# cf2loco.net
KiCad netlist of a schematic drawn in Altium Designer
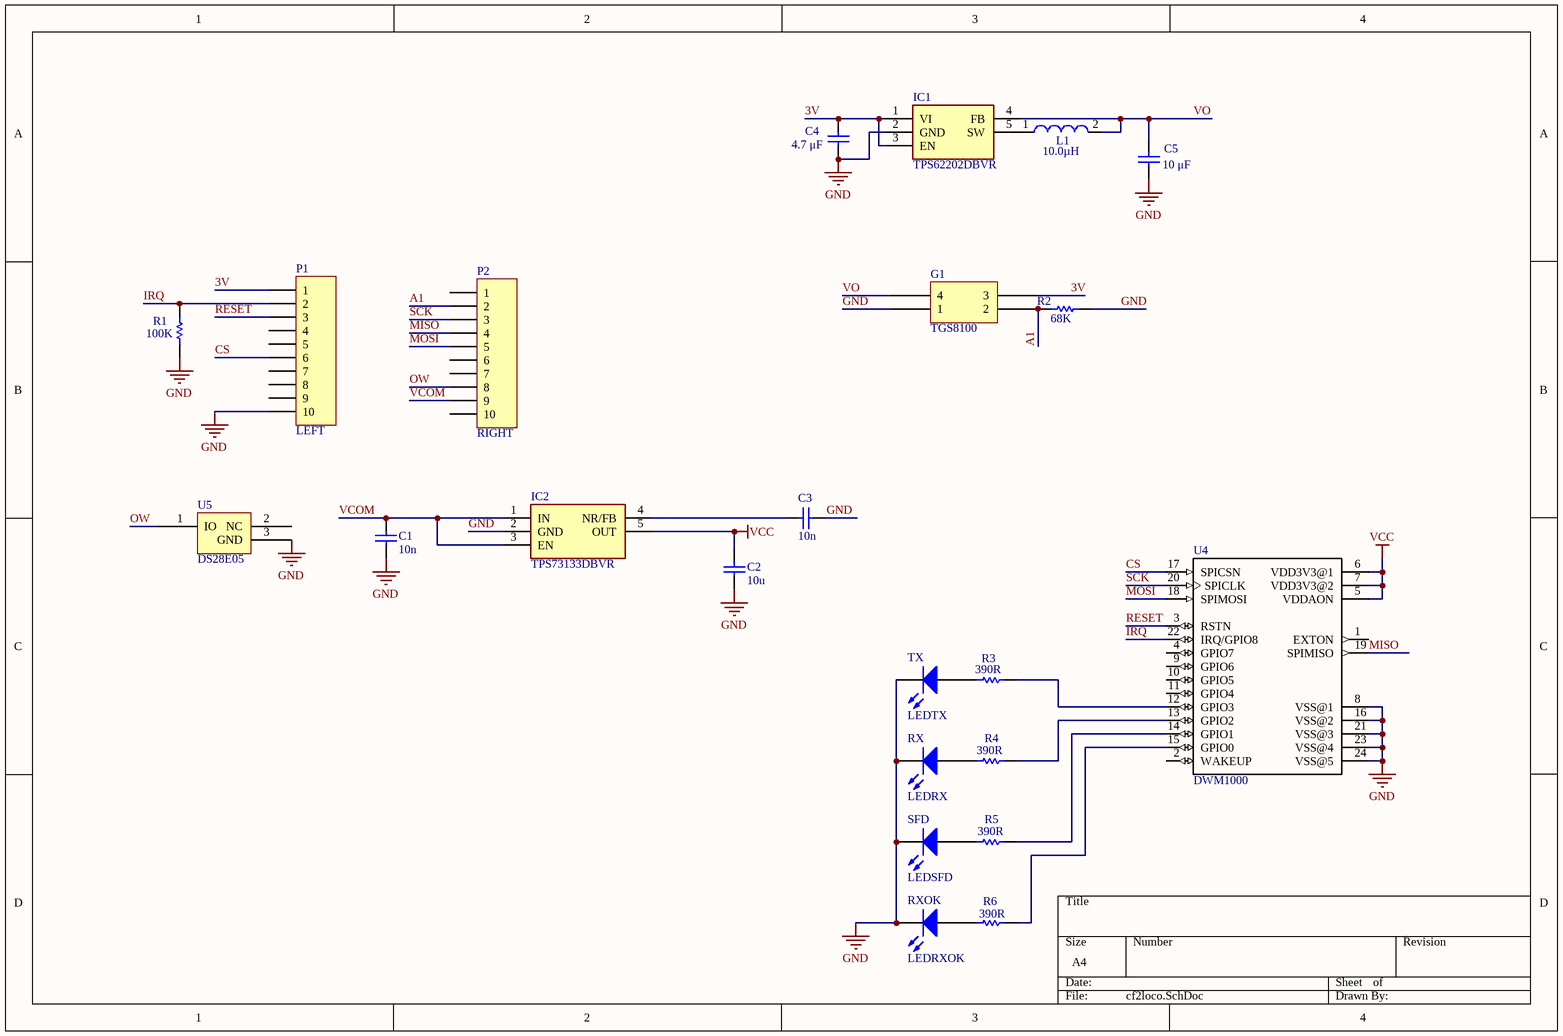
[diagram p0: cf2loco.SchDoc]

(export (version "E")
  (design (tool "Eeschema 10.0.6"))
  (components
    (comp (ref "C1")
      (value "10n")
      (footprint "0402-A")
      (description "Capacitor")
      (fields (field (name "Comment") "Cap") (field (name "PUBLISHER") "Altium Limited"))
      (libsource (lib "Miscellaneous Devices") (part "Cap"))
    )
    (comp (ref "C2")
      (value "10u")
      (footprint "0603")
      (description "Capacitor")
      (fields (field (name "Comment") "Cap") (field (name "PUBLISHER") "Altium Limited"))
      (libsource (lib "Miscellaneous Devices") (part "Cap"))
    )
    (comp (ref "C3")
      (value "10n")
      (footprint "0402-A")
      (description "Capacitor")
      (fields (field (name "Comment") "Cap") (field (name "PUBLISHER") "Altium Limited"))
      (libsource (lib "Miscellaneous Devices") (part "Cap"))
    )
    (comp (ref "C4")
      (value "06036D475KAT2A")
      (footprint "CAPC1608X90X35LL15T15")
      (fields (field (name "MANUFACTURER") "AVX Interconnect / Elco") (field (name "PARAMETER 1") "4.7 μF"))
      (libsource (lib "Altium Content Vault") (part "CAP"))
    )
    (comp (ref "C5")
      (value "06036D106MAT2A")
      (footprint "CAPC1608X90X35ML15T15")
      (fields (field (name "MANUFACTURER") "AVX Interconnect / Elco") (field (name "PARAMETER 1") "10 μF"))
      (libsource (lib "Altium Content Vault") (part "CAP"))
    )
    (comp (ref "G1") (value "TGS8100") (footprint "TGS8100") (libsource (lib "cf2loco") (part "TGS8100")))
    (comp (ref "IC1")
      (value "TPS62202DBVR")
      (footprint "SamacSys:SOT95P280X145-5N")
      (description "Integrated Circuit")
      (libsource (lib "*") (part "TPS62202DBVR"))
    )
    (comp (ref "IC2")
      (value "TPS73133DBVR")
      (footprint "SamacSys:SOT95P280X145-5N")
      (description "Integrated Circuit")
      (fields (field (name "MOUSER2 PART NUMBER") "595-TPS73133DBVR"))
      (libsource (lib "*") (part "TPS73133DBVR"))
    )
    (comp (ref "L1")
      (value "744031100")
      (footprint "WE-TPC-3816-S")
      (description "SMD Shielded Tiny Power Inductor WE-TPC, L = 10.0 µH")
      (fields (field (name "INDUCTANCE") "10.0µH"))
      (libsource (lib "Altium Content Vault") (part "PAS-IND-INDUCTOR-2"))
    )
    (comp (ref "P1")
      (value "LEFT")
      (footprint "CFHEADER")
      (description "Header, 10-Pin")
      (fields (field (name "PUBLISHER") "Altium Limited"))
      (libsource (lib "Miscellaneous Connectors") (part "Header 10"))
    )
    (comp (ref "P2")
      (value "RIGHT")
      (footprint "CFHEADER")
      (description "Header, 10-Pin")
      (fields (field (name "PUBLISHER") "Altium Limited"))
      (libsource (lib "Miscellaneous Connectors") (part "Header 10"))
    )
    (comp (ref "R1")
      (value "CRCW0805100KFKEA")
      (footprint "RESC2013X50X30NL20T20")
      (fields (field (name "MANUFACTURER") "Vishay Dale") (field (name "PARAMETER 1") "100K"))
      (libsource (lib "Altium Content Vault") (part "RES"))
    )
    (comp (ref "R2")
      (value "68K")
      (footprint "RESC0603(1608)_M")
      (description "68K 0.1W 1% 0603 (1608 Metric)  SMD")
      (fields (field (name "POWER") "0.1 W") (field (name "TOLERANCE") "1 %"))
      (libsource (lib "Altium Content Vault") (part "RES"))
    )
    (comp (ref "R3")
      (value "CRCW0805390RFKEA")
      (footprint "RESC2013X50X30NL20T20")
      (fields (field (name "MANUFACTURER") "Vishay Dale") (field (name "PARAMETER 1") "390R"))
      (libsource (lib "Altium Content Vault") (part "RES"))
    )
    (comp (ref "R4")
      (value "CRCW0805390RFKEA")
      (footprint "RESC2013X50X30NL20T20")
      (fields (field (name "MANUFACTURER") "Vishay Dale") (field (name "PARAMETER 1") "390R"))
      (libsource (lib "Altium Content Vault") (part "RES"))
    )
    (comp (ref "R5")
      (value "CRCW0805390RFKEA")
      (footprint "RESC2013X50X30NL20T20")
      (fields (field (name "MANUFACTURER") "Vishay Dale") (field (name "PARAMETER 1") "390R"))
      (libsource (lib "Altium Content Vault") (part "RES"))
    )
    (comp (ref "R6")
      (value "CRCW0805390RFKEA")
      (footprint "RESC2013X50X30NL20T20")
      (fields (field (name "MANUFACTURER") "Vishay Dale") (field (name "PARAMETER 1") "390R"))
      (libsource (lib "Altium Content Vault") (part "RES"))
    )
    (comp (ref "RX")
      (value "LEDRX")
      (footprint "0402-A")
      (description "Typical RED, GREEN, YELLOW, AMBER GaAs LED")
      (fields (field (name "PUBLISHER") "Altium Limited"))
      (libsource (lib "Miscellaneous Devices") (part "LED2"))
    )
    (comp (ref "RXOK")
      (value "LEDRXOK")
      (footprint "0402-A")
      (description "Typical RED, GREEN, YELLOW, AMBER GaAs LED")
      (fields (field (name "PUBLISHER") "Altium Limited"))
      (libsource (lib "Miscellaneous Devices") (part "LED2"))
    )
    (comp (ref "SFD")
      (value "LEDSFD")
      (footprint "0402-A")
      (description "Typical RED, GREEN, YELLOW, AMBER GaAs LED")
      (fields (field (name "PUBLISHER") "Altium Limited"))
      (libsource (lib "Miscellaneous Devices") (part "LED2"))
    )
    (comp (ref "TX")
      (value "LEDTX")
      (footprint "0402-A")
      (description "Typical RED, GREEN, YELLOW, AMBER GaAs LED")
      (fields (field (name "PUBLISHER") "Altium Limited"))
      (libsource (lib "Miscellaneous Devices") (part "LED2"))
    )
    (comp (ref "U4")
      (value "DWM1000")
      (footprint "DECW-DWM1000-24_V")
      (description "Mod Ieee802.15.4-2011 Uwb Txrx")
      (fields (field (name "MF") "Decawave"))
      (libsource (lib "DWM1000") (part "DWM1000"))
    )
    (comp (ref "U5") (value "DS28E05") (footprint "SOT23") (libsource (lib "cf2loco") (part "DS28E05")))
  )
  (nets
    (net (code "1") (name "/3V") (class "Default")
      (node (ref "C4") (pin "2") (pinfunction "2_2") (pintype "passive"))
      (node (ref "G1") (pin "3") (pinfunction "3_3") (pintype "passive"))
      (node (ref "IC1") (pin "1") (pinfunction "VI_1") (pintype "passive"))
      (node (ref "IC1") (pin "3") (pinfunction "EN_3") (pintype "passive"))
      (node (ref "P1") (pin "1") (pinfunction "1_1") (pintype "passive"))
    )
    (net (code "2") (name "/A1") (class "Default")
      (node (ref "G1") (pin "2") (pinfunction "2_2") (pintype "passive"))
      (node (ref "P2") (pin "2") (pinfunction "2_2") (pintype "passive"))
      (node (ref "R2") (pin "1") (pinfunction "1_1") (pintype "passive"))
    )
    (net (code "3") (name "/CS") (class "Default")
      (node (ref "P1") (pin "6") (pinfunction "6_6") (pintype "passive"))
      (node (ref "U4") (pin "17") (pinfunction "SPICSN_17") (pintype "input"))
    )
    (net (code "4") (name "/IRQ") (class "Default")
      (node (ref "P1") (pin "2") (pinfunction "2_2") (pintype "passive"))
      (node (ref "R1") (pin "2") (pinfunction "2_2") (pintype "passive"))
      (node (ref "U4") (pin "22") (pinfunction "IRQ/GPIO8_22") (pintype "bidirectional"))
    )
    (net (code "5") (name "/MISO") (class "Default")
      (node (ref "P2") (pin "4") (pinfunction "4_4") (pintype "passive"))
      (node (ref "U4") (pin "19") (pinfunction "SPIMISO_19") (pintype "output"))
    )
    (net (code "6") (name "/MOSI") (class "Default")
      (node (ref "P2") (pin "5") (pinfunction "5_5") (pintype "passive"))
      (node (ref "U4") (pin "18") (pinfunction "SPIMOSI_18") (pintype "input"))
    )
    (net (code "7") (name "/OW") (class "Default")
      (node (ref "P2") (pin "8") (pinfunction "8_8") (pintype "passive"))
      (node (ref "U5") (pin "1") (pinfunction "IO_1") (pintype "passive"))
    )
    (net (code "8") (name "/RESET") (class "Default")
      (node (ref "P1") (pin "3") (pinfunction "3_3") (pintype "passive"))
      (node (ref "U4") (pin "3") (pinfunction "RSTN_3") (pintype "bidirectional"))
    )
    (net (code "9") (name "/SCK") (class "Default")
      (node (ref "P2") (pin "3") (pinfunction "3_3") (pintype "passive"))
      (node (ref "U4") (pin "20") (pinfunction "SPICLK_20") (pintype "input"))
    )
    (net (code "10") (name "/VCOM") (class "Default")
      (node (ref "C1") (pin "2") (pinfunction "2_2") (pintype "passive"))
      (node (ref "IC2") (pin "1") (pinfunction "IN_1") (pintype "passive"))
      (node (ref "IC2") (pin "3") (pinfunction "EN_3") (pintype "passive"))
      (node (ref "P2") (pin "9") (pinfunction "9_9") (pintype "passive"))
    )
    (net (code "11") (name "/VO") (class "Default")
      (node (ref "C5") (pin "2") (pinfunction "2_2") (pintype "passive"))
      (node (ref "G1") (pin "4") (pinfunction "4_4") (pintype "passive"))
      (node (ref "IC1") (pin "4") (pinfunction "FB_4") (pintype "passive"))
      (node (ref "L1") (pin "2") (pinfunction "2_2") (pintype "passive"))
    )
    (net (code "12") (name "GND") (class "Default")
      (node (ref "C1") (pin "1") (pinfunction "1_1") (pintype "passive"))
      (node (ref "C2") (pin "1") (pinfunction "1_1") (pintype "passive"))
      (node (ref "C3") (pin "2") (pinfunction "2_2") (pintype "passive"))
      (node (ref "C4") (pin "1") (pinfunction "1_1") (pintype "passive"))
      (node (ref "C5") (pin "1") (pinfunction "1_1") (pintype "passive"))
      (node (ref "G1") (pin "1") (pinfunction "1_1") (pintype "passive"))
      (node (ref "IC1") (pin "2") (pinfunction "GND_2") (pintype "passive"))
      (node (ref "IC2") (pin "2") (pinfunction "GND_2") (pintype "passive"))
      (node (ref "P1") (pin "10") (pinfunction "10_10") (pintype "passive"))
      (node (ref "R1") (pin "1") (pinfunction "1_1") (pintype "passive"))
      (node (ref "R2") (pin "2") (pinfunction "2_2") (pintype "passive"))
      (node (ref "RX") (pin "2") (pinfunction "K_2") (pintype "passive"))
      (node (ref "RXOK") (pin "2") (pinfunction "K_2") (pintype "passive"))
      (node (ref "SFD") (pin "2") (pinfunction "K_2") (pintype "passive"))
      (node (ref "TX") (pin "2") (pinfunction "K_2") (pintype "passive"))
      (node (ref "U4") (pin "16") (pinfunction "VSS@2_16") (pintype "power_in"))
      (node (ref "U4") (pin "21") (pinfunction "VSS@3_21") (pintype "power_in"))
      (node (ref "U4") (pin "23") (pinfunction "VSS@4_23") (pintype "power_in"))
      (node (ref "U4") (pin "24") (pinfunction "VSS@5_24") (pintype "power_in"))
      (node (ref "U4") (pin "8") (pinfunction "VSS@1_8") (pintype "power_in"))
      (node (ref "U5") (pin "3") (pinfunction "GND_3") (pintype "passive"))
    )
    (net (code "13") (name "Net-(IC1-SW)") (class "Default")
      (node (ref "IC1") (pin "5") (pinfunction "SW_5") (pintype "passive"))
      (node (ref "L1") (pin "1") (pinfunction "1_1") (pintype "passive"))
    )
    (net (code "14") (name "Net-(IC2-NR{slash}FB)") (class "Default")
      (node (ref "C3") (pin "1") (pinfunction "1_1") (pintype "passive"))
      (node (ref "IC2") (pin "4") (pinfunction "NR/FB_4") (pintype "passive"))
    )
    (net (code "15") (name "Net-(RX-A)") (class "Default")
      (node (ref "R4") (pin "1") (pinfunction "1_1") (pintype "passive"))
      (node (ref "RX") (pin "1") (pinfunction "A_1") (pintype "passive"))
    )
    (net (code "16") (name "Net-(RXOK-A)") (class "Default")
      (node (ref "R6") (pin "1") (pinfunction "1_1") (pintype "passive"))
      (node (ref "RXOK") (pin "1") (pinfunction "A_1") (pintype "passive"))
    )
    (net (code "17") (name "Net-(SFD-A)") (class "Default")
      (node (ref "R5") (pin "1") (pinfunction "1_1") (pintype "passive"))
      (node (ref "SFD") (pin "1") (pinfunction "A_1") (pintype "passive"))
    )
    (net (code "18") (name "Net-(TX-A)") (class "Default")
      (node (ref "R3") (pin "1") (pinfunction "1_1") (pintype "passive"))
      (node (ref "TX") (pin "1") (pinfunction "A_1") (pintype "passive"))
    )
    (net (code "19") (name "Net-(U4-GPIO0)") (class "Default")
      (node (ref "R6") (pin "2") (pinfunction "2_2") (pintype "passive"))
      (node (ref "U4") (pin "15") (pinfunction "GPIO0_15") (pintype "bidirectional"))
    )
    (net (code "20") (name "Net-(U4-GPIO1)") (class "Default")
      (node (ref "R5") (pin "2") (pinfunction "2_2") (pintype "passive"))
      (node (ref "U4") (pin "14") (pinfunction "GPIO1_14") (pintype "bidirectional"))
    )
    (net (code "21") (name "Net-(U4-GPIO2)") (class "Default")
      (node (ref "R4") (pin "2") (pinfunction "2_2") (pintype "passive"))
      (node (ref "U4") (pin "13") (pinfunction "GPIO2_13") (pintype "bidirectional"))
    )
    (net (code "22") (name "Net-(U4-GPIO3)") (class "Default")
      (node (ref "R3") (pin "2") (pinfunction "2_2") (pintype "passive"))
      (node (ref "U4") (pin "12") (pinfunction "GPIO3_12") (pintype "bidirectional"))
    )
    (net (code "23") (name "VCC") (class "Default")
      (node (ref "C2") (pin "2") (pinfunction "2_2") (pintype "passive"))
      (node (ref "IC2") (pin "5") (pinfunction "OUT_5") (pintype "passive"))
      (node (ref "U4") (pin "5") (pinfunction "VDDAON_5") (pintype "power_in"))
      (node (ref "U4") (pin "6") (pinfunction "VDD3V3@1_6") (pintype "power_in"))
      (node (ref "U4") (pin "7") (pinfunction "VDD3V3@2_7") (pintype "power_in"))
    )
    (net (code "24") (name "unconnected-(P1-Pad4)") (class "Default")
      (node (ref "P1") (pin "4") (pinfunction "4_4") (pintype "passive"))
    )
    (net (code "25") (name "unconnected-(P1-Pad5)") (class "Default")
      (node (ref "P1") (pin "5") (pinfunction "5_5") (pintype "passive"))
    )
    (net (code "26") (name "unconnected-(P1-Pad7)") (class "Default")
      (node (ref "P1") (pin "7") (pinfunction "7_7") (pintype "passive"))
    )
    (net (code "27") (name "unconnected-(P1-Pad8)") (class "Default")
      (node (ref "P1") (pin "8") (pinfunction "8_8") (pintype "passive"))
    )
    (net (code "28") (name "unconnected-(P1-Pad9)") (class "Default")
      (node (ref "P1") (pin "9") (pinfunction "9_9") (pintype "passive"))
    )
    (net (code "29") (name "unconnected-(P2-Pad1)") (class "Default")
      (node (ref "P2") (pin "1") (pinfunction "1_1") (pintype "passive"))
    )
    (net (code "30") (name "unconnected-(P2-Pad6)") (class "Default")
      (node (ref "P2") (pin "6") (pinfunction "6_6") (pintype "passive"))
    )
    (net (code "31") (name "unconnected-(P2-Pad7)") (class "Default")
      (node (ref "P2") (pin "7") (pinfunction "7_7") (pintype "passive"))
    )
    (net (code "32") (name "unconnected-(P2-Pad10)") (class "Default")
      (node (ref "P2") (pin "10") (pinfunction "10_10") (pintype "passive"))
    )
    (net (code "33") (name "unconnected-(U4-EXTON-Pad1)") (class "Default")
      (node (ref "U4") (pin "1") (pinfunction "EXTON_1") (pintype "output"))
    )
    (net (code "34") (name "unconnected-(U4-GPIO4-Pad11)") (class "Default")
      (node (ref "U4") (pin "11") (pinfunction "GPIO4_11") (pintype "bidirectional"))
    )
    (net (code "35") (name "unconnected-(U4-GPIO5-Pad10)") (class "Default")
      (node (ref "U4") (pin "10") (pinfunction "GPIO5_10") (pintype "bidirectional"))
    )
    (net (code "36") (name "unconnected-(U4-GPIO6-Pad9)") (class "Default")
      (node (ref "U4") (pin "9") (pinfunction "GPIO6_9") (pintype "bidirectional"))
    )
    (net (code "37") (name "unconnected-(U4-GPIO7-Pad4)") (class "Default")
      (node (ref "U4") (pin "4") (pinfunction "GPIO7_4") (pintype "bidirectional"))
    )
    (net (code "38") (name "unconnected-(U4-WAKEUP-Pad2)") (class "Default")
      (node (ref "U4") (pin "2") (pinfunction "WAKEUP_2") (pintype "bidirectional"))
    )
    (net (code "39") (name "unconnected-(U5-NC-Pad2)") (class "Default")
      (node (ref "U5") (pin "2") (pinfunction "NC_2") (pintype "passive"))
    )
  )
)
